# AmiExtFDD.net
KiCad netlist of a schematic drawn in EAGLE
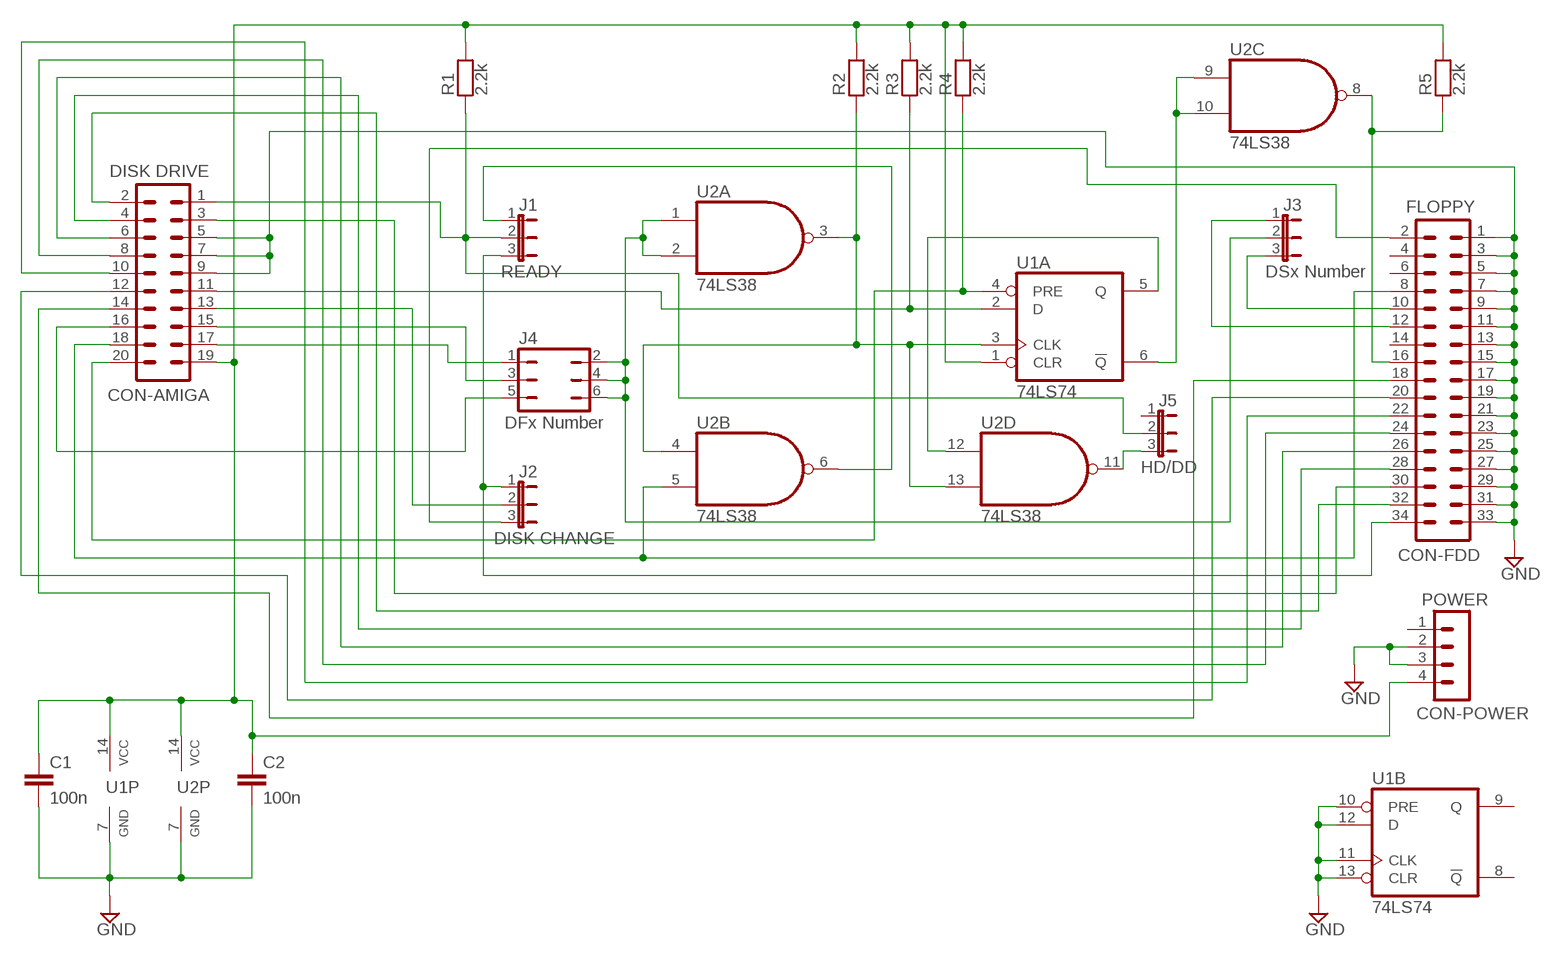
[diagram p0: schematic, sheet 1]

(export (version "E")
  (design (tool "Eeschema 10.0.6"))
  (components
    (comp (ref "C1")
      (value "100n")
      (footprint "eagle-import:SMD-UNI")
      (libsource (lib "eagle-import") (part "PAD-C5SMD"))
    )
    (comp (ref "C2")
      (value "100n")
      (footprint "eagle-import:SMD-UNI")
      (libsource (lib "eagle-import") (part "PAD-C5SMD"))
    )
    (comp (ref "CON-AMIGA")
      (value "DISK DRIVE")
      (footprint "eagle-import:IDC20")
      (libsource (lib "eagle-import") (part "IDC20"))
    )
    (comp (ref "CON-FDD")
      (value "FLOPPY")
      (footprint "eagle-import:FDD2")
      (libsource (lib "eagle-import") (part "FDD2"))
    )
    (comp (ref "CON-POWER")
      (value "POWER")
      (footprint "eagle-import:MINI-MOLEX")
      (libsource (lib "eagle-import") (part "MIN-MOLEX"))
    )
    (comp (ref "J1")
      (value "READY")
      (footprint "eagle-import:JP3X1-UNI")
      (libsource (lib "eagle-import") (part "PAD-JP3X1UNI"))
    )
    (comp (ref "J2")
      (value "DISK CHANGE")
      (footprint "eagle-import:JP3X1-UNI")
      (libsource (lib "eagle-import") (part "PAD-JP3X1UNI"))
    )
    (comp (ref "J3")
      (value "DSx Number")
      (footprint "eagle-import:JP3X1-UNI")
      (libsource (lib "eagle-import") (part "PAD-JP3X1UNI"))
    )
    (comp (ref "J4")
      (value "DFx Number")
      (footprint "eagle-import:JP3X2-UNI")
      (libsource (lib "eagle-import") (part "PAD-JP3X2UNI"))
    )
    (comp (ref "J5")
      (value "HD/DD")
      (footprint "eagle-import:JP3X1-UNI")
      (libsource (lib "eagle-import") (part "PAD-JP3X1UNI"))
    )
    (comp (ref "R1")
      (value "2.2k")
      (footprint "eagle-import:SMD-UNI")
      (libsource (lib "eagle-import") (part "PAD-R10SMD"))
    )
    (comp (ref "R2")
      (value "2.2k")
      (footprint "eagle-import:SMD-UNI")
      (libsource (lib "eagle-import") (part "PAD-R10SMD"))
    )
    (comp (ref "R3")
      (value "2.2k")
      (footprint "eagle-import:SMD-UNI")
      (libsource (lib "eagle-import") (part "PAD-R10SMD"))
    )
    (comp (ref "R4")
      (value "2.2k")
      (footprint "eagle-import:SMD-UNI")
      (libsource (lib "eagle-import") (part "PAD-R10SMD"))
    )
    (comp (ref "R5")
      (value "2.2k")
      (footprint "eagle-import:SMD-UNI")
      (libsource (lib "eagle-import") (part "PAD-R10SMD"))
    )
    (comp (ref "U1")
      (value "74LS74")
      (footprint "eagle-import:SO14")
      (libsource (lib "eagle-import") (part "PAD-7474SO14"))
    )
    (comp (ref "U2")
      (value "74LS38")
      (footprint "eagle-import:SO14")
      (libsource (lib "eagle-import") (part "PAD-7438SO14"))
    )
  )
  (nets
    (net (code "1") (name "/1") (class "Default")
      (node (ref "CON-POWER") (pin "1") (pinfunction "1_1") (pintype "power_in"))
    )
    (net (code "2") (name "GND") (class "Default")
      (node (ref "C1") (pin "2") (pinfunction "2_2") (pintype "passive"))
      (node (ref "C2") (pin "2") (pinfunction "2_2") (pintype "passive"))
      (node (ref "CON-AMIGA") (pin "5") (pinfunction "5_5") (pintype "passive"))
      (node (ref "CON-AMIGA") (pin "7") (pinfunction "7_7") (pintype "passive"))
      (node (ref "CON-AMIGA") (pin "9") (pinfunction "9_9") (pintype "power_in"))
      (node (ref "CON-FDD") (pin "1") (pinfunction "1_1") (pintype "passive"))
      (node (ref "CON-FDD") (pin "11") (pinfunction "11_11") (pintype "passive"))
      (node (ref "CON-FDD") (pin "13") (pinfunction "13_13") (pintype "passive"))
      (node (ref "CON-FDD") (pin "15") (pinfunction "15_15") (pintype "passive"))
      (node (ref "CON-FDD") (pin "17") (pinfunction "17_17") (pintype "passive"))
      (node (ref "CON-FDD") (pin "19") (pinfunction "19_19") (pintype "passive"))
      (node (ref "CON-FDD") (pin "21") (pinfunction "21_21") (pintype "passive"))
      (node (ref "CON-FDD") (pin "23") (pinfunction "23_23") (pintype "passive"))
      (node (ref "CON-FDD") (pin "25") (pinfunction "25_25") (pintype "passive"))
      (node (ref "CON-FDD") (pin "27") (pinfunction "27_27") (pintype "passive"))
      (node (ref "CON-FDD") (pin "29") (pinfunction "29_29") (pintype "passive"))
      (node (ref "CON-FDD") (pin "3") (pinfunction "3_3") (pintype "passive"))
      (node (ref "CON-FDD") (pin "31") (pinfunction "31_31") (pintype "passive"))
      (node (ref "CON-FDD") (pin "33") (pinfunction "33_33") (pintype "passive"))
      (node (ref "CON-FDD") (pin "5") (pinfunction "5_5") (pintype "passive"))
      (node (ref "CON-FDD") (pin "7") (pinfunction "7_7") (pintype "passive"))
      (node (ref "CON-FDD") (pin "9") (pinfunction "9_9") (pintype "passive"))
      (node (ref "CON-POWER") (pin "2") (pinfunction "2_2") (pintype "power_in"))
      (node (ref "CON-POWER") (pin "3") (pinfunction "3_3") (pintype "power_in"))
      (node (ref "U1") (pin "10") (pinfunction "PRE_10") (pintype "input"))
      (node (ref "U1") (pin "11") (pinfunction "CLK_11") (pintype "input"))
      (node (ref "U1") (pin "12") (pinfunction "D_12") (pintype "input"))
      (node (ref "U1") (pin "13") (pinfunction "CLR_13") (pintype "input"))
      (node (ref "U1") (pin "7") (pinfunction "GND_7") (pintype "power_in"))
      (node (ref "U2") (pin "7") (pinfunction "GND_7") (pintype "power_in"))
    )
    (net (code "3") (name "Net-(CON-AMIGA-Pad1)") (class "Default")
      (node (ref "CON-AMIGA") (pin "1") (pinfunction "1_1") (pintype "power_in"))
      (node (ref "J1") (pin "2") (pinfunction "2_2") (pintype "passive"))
      (node (ref "J5") (pin "2") (pinfunction "2_2") (pintype "passive"))
      (node (ref "R1") (pin "1") (pinfunction "1_1") (pintype "passive"))
    )
    (net (code "4") (name "Net-(CON-AMIGA-Pad2)") (class "Default")
      (node (ref "CON-AMIGA") (pin "2") (pinfunction "2_2") (pintype "passive"))
      (node (ref "CON-FDD") (pin "32") (pinfunction "32_32") (pintype "passive"))
    )
    (net (code "5") (name "Net-(CON-AMIGA-Pad3)") (class "Default")
      (node (ref "CON-AMIGA") (pin "3") (pinfunction "3_3") (pintype "passive"))
      (node (ref "CON-FDD") (pin "30") (pinfunction "30_30") (pintype "passive"))
    )
    (net (code "6") (name "Net-(CON-AMIGA-Pad4)") (class "Default")
      (node (ref "CON-AMIGA") (pin "4") (pinfunction "4_4") (pintype "passive"))
      (node (ref "CON-FDD") (pin "28") (pinfunction "28_28") (pintype "passive"))
    )
    (net (code "7") (name "Net-(CON-AMIGA-Pad6)") (class "Default")
      (node (ref "CON-AMIGA") (pin "6") (pinfunction "6_6") (pintype "passive"))
      (node (ref "CON-FDD") (pin "26") (pinfunction "26_26") (pintype "passive"))
    )
    (net (code "8") (name "Net-(CON-AMIGA-Pad8)") (class "Default")
      (node (ref "CON-AMIGA") (pin "8") (pinfunction "8_8") (pintype "passive"))
      (node (ref "CON-FDD") (pin "24") (pinfunction "24_24") (pintype "passive"))
    )
    (net (code "9") (name "Net-(CON-AMIGA-Pad10)") (class "Default")
      (node (ref "CON-AMIGA") (pin "10") (pinfunction "10_10") (pintype "passive"))
      (node (ref "CON-FDD") (pin "22") (pinfunction "22_22") (pintype "passive"))
    )
    (net (code "10") (name "Net-(CON-AMIGA-Pad12)") (class "Default")
      (node (ref "CON-AMIGA") (pin "12") (pinfunction "12_12") (pintype "passive"))
      (node (ref "CON-FDD") (pin "20") (pinfunction "20_20") (pintype "passive"))
    )
    (net (code "11") (name "Net-(CON-AMIGA-Pad13)") (class "Default")
      (node (ref "CON-AMIGA") (pin "13") (pinfunction "13_13") (pintype "passive"))
      (node (ref "J2") (pin "2") (pinfunction "2_2") (pintype "passive"))
    )
    (net (code "12") (name "Net-(CON-AMIGA-Pad14)") (class "Default")
      (node (ref "CON-AMIGA") (pin "14") (pinfunction "14_14") (pintype "passive"))
      (node (ref "CON-FDD") (pin "18") (pinfunction "18_18") (pintype "passive"))
    )
    (net (code "13") (name "Net-(CON-AMIGA-Pad15)") (class "Default")
      (node (ref "CON-AMIGA") (pin "15") (pinfunction "15_15") (pintype "passive"))
      (node (ref "J4") (pin "3") (pinfunction "3_3") (pintype "passive"))
    )
    (net (code "14") (name "Net-(CON-AMIGA-Pad16)") (class "Default")
      (node (ref "CON-AMIGA") (pin "16") (pinfunction "16_16") (pintype "passive"))
      (node (ref "J4") (pin "5") (pinfunction "5_5") (pintype "passive"))
    )
    (net (code "15") (name "Net-(CON-AMIGA-Pad17)") (class "Default")
      (node (ref "CON-AMIGA") (pin "17") (pinfunction "17_17") (pintype "passive"))
      (node (ref "J4") (pin "1") (pinfunction "1_1") (pintype "passive"))
    )
    (net (code "16") (name "Net-(CON-FDD-Pad2)") (class "Default")
      (node (ref "CON-FDD") (pin "2") (pinfunction "2_2") (pintype "passive"))
      (node (ref "J2") (pin "3") (pinfunction "3_3") (pintype "passive"))
    )
    (net (code "17") (name "Net-(CON-FDD-Pad10)") (class "Default")
      (node (ref "CON-FDD") (pin "10") (pinfunction "10_10") (pintype "passive"))
      (node (ref "J3") (pin "3") (pinfunction "3_3") (pintype "passive"))
    )
    (net (code "18") (name "Net-(CON-FDD-Pad12)") (class "Default")
      (node (ref "CON-FDD") (pin "12") (pinfunction "12_12") (pintype "passive"))
      (node (ref "J3") (pin "1") (pinfunction "1_1") (pintype "passive"))
    )
    (net (code "19") (name "Net-(CON-FDD-Pad34)") (class "Default")
      (node (ref "CON-FDD") (pin "34") (pinfunction "34_34") (pintype "passive"))
      (node (ref "J1") (pin "3") (pinfunction "3_3") (pintype "passive"))
      (node (ref "J2") (pin "1") (pinfunction "1_1") (pintype "passive"))
    )
    (net (code "20") (name "Net-(U1A-CLK)") (class "Default")
      (node (ref "R2") (pin "1") (pinfunction "1_1") (pintype "passive"))
      (node (ref "U1") (pin "3") (pinfunction "CLK_3") (pintype "input"))
      (node (ref "U2") (pin "13") (pinfunction "I1_13") (pintype "input"))
      (node (ref "U2") (pin "3") (pinfunction "O_3") (pintype "output"))
      (node (ref "U2") (pin "4") (pinfunction "I0_4") (pintype "input"))
    )
    (net (code "21") (name "Net-(U1A-CLR)") (class "Default")
      (node (ref "C1") (pin "1") (pinfunction "1_1") (pintype "passive"))
      (node (ref "C2") (pin "1") (pinfunction "1_1") (pintype "passive"))
      (node (ref "CON-AMIGA") (pin "19") (pinfunction "19_19") (pintype "passive"))
      (node (ref "CON-POWER") (pin "4") (pinfunction "4_4") (pintype "power_in"))
      (node (ref "R1") (pin "2") (pinfunction "2_2") (pintype "passive"))
      (node (ref "R2") (pin "2") (pinfunction "2_2") (pintype "passive"))
      (node (ref "R3") (pin "2") (pinfunction "2_2") (pintype "passive"))
      (node (ref "R4") (pin "2") (pinfunction "2_2") (pintype "passive"))
      (node (ref "R5") (pin "2") (pinfunction "2_2") (pintype "passive"))
      (node (ref "U1") (pin "1") (pinfunction "CLR_1") (pintype "input"))
      (node (ref "U1") (pin "14") (pinfunction "VCC_14") (pintype "power_in"))
      (node (ref "U2") (pin "14") (pinfunction "VCC_14") (pintype "power_in"))
    )
    (net (code "22") (name "Net-(U1A-D)") (class "Default")
      (node (ref "CON-AMIGA") (pin "11") (pinfunction "11_11") (pintype "passive"))
      (node (ref "R3") (pin "1") (pinfunction "1_1") (pintype "passive"))
      (node (ref "U1") (pin "2") (pinfunction "D_2") (pintype "input"))
    )
    (net (code "23") (name "Net-(U1A-PRE)") (class "Default")
      (node (ref "CON-AMIGA") (pin "20") (pinfunction "20_20") (pintype "passive"))
      (node (ref "R4") (pin "1") (pinfunction "1_1") (pintype "passive"))
      (node (ref "U1") (pin "4") (pinfunction "PRE_4") (pintype "input"))
    )
    (net (code "24") (name "Net-(U1A-Q)") (class "Default")
      (node (ref "U1") (pin "5") (pinfunction "Q_5") (pintype "output"))
      (node (ref "U2") (pin "12") (pinfunction "I0_12") (pintype "input"))
    )
    (net (code "25") (name "Net-(U1A-~{Q})") (class "Default")
      (node (ref "U1") (pin "6") (pinfunction "~{Q}_6") (pintype "output"))
      (node (ref "U2") (pin "10") (pinfunction "I1_10") (pintype "input"))
      (node (ref "U2") (pin "9") (pinfunction "I0_9") (pintype "input"))
    )
    (net (code "26") (name "Net-(U2A-I0)") (class "Default")
      (node (ref "J3") (pin "2") (pinfunction "2_2") (pintype "passive"))
      (node (ref "J4") (pin "2") (pinfunction "2_2") (pintype "passive"))
      (node (ref "J4") (pin "4") (pinfunction "4_4") (pintype "passive"))
      (node (ref "J4") (pin "6") (pinfunction "6_6") (pintype "passive"))
      (node (ref "U2") (pin "1") (pinfunction "I0_1") (pintype "input"))
      (node (ref "U2") (pin "2") (pinfunction "I1_2") (pintype "input"))
    )
    (net (code "27") (name "Net-(U2B-I1)") (class "Default")
      (node (ref "CON-AMIGA") (pin "18") (pinfunction "18_18") (pintype "passive"))
      (node (ref "CON-FDD") (pin "8") (pinfunction "8_8") (pintype "passive"))
      (node (ref "U2") (pin "5") (pinfunction "I1_5") (pintype "input"))
    )
    (net (code "28") (name "Net-(U2B-O)") (class "Default")
      (node (ref "J1") (pin "1") (pinfunction "1_1") (pintype "passive"))
      (node (ref "U2") (pin "6") (pinfunction "O_6") (pintype "output"))
    )
    (net (code "29") (name "Net-(U2C-O)") (class "Default")
      (node (ref "CON-FDD") (pin "16") (pinfunction "16_16") (pintype "passive"))
      (node (ref "R5") (pin "1") (pinfunction "1_1") (pintype "passive"))
      (node (ref "U2") (pin "8") (pinfunction "O_8") (pintype "output"))
    )
    (net (code "30") (name "Net-(U2D-O)") (class "Default")
      (node (ref "J5") (pin "3") (pinfunction "3_3") (pintype "passive"))
      (node (ref "U2") (pin "11") (pinfunction "O_11") (pintype "output"))
    )
    (net (code "31") (name "unconnected-(CON-FDD-Pad4)") (class "Default")
      (node (ref "CON-FDD") (pin "4") (pinfunction "4_4") (pintype "passive"))
    )
    (net (code "32") (name "unconnected-(CON-FDD-Pad6)") (class "Default")
      (node (ref "CON-FDD") (pin "6") (pinfunction "6_6") (pintype "passive"))
    )
    (net (code "33") (name "unconnected-(CON-FDD-Pad14)") (class "Default")
      (node (ref "CON-FDD") (pin "14") (pinfunction "14_14") (pintype "passive"))
    )
    (net (code "34") (name "unconnected-(J5-Pad1)") (class "Default")
      (node (ref "J5") (pin "1") (pinfunction "1_1") (pintype "passive"))
    )
    (net (code "35") (name "unconnected-(U1B-Q-Pad9)") (class "Default")
      (node (ref "U1") (pin "9") (pinfunction "Q_9") (pintype "output"))
    )
    (net (code "36") (name "unconnected-(U1B-~{Q}-Pad8)") (class "Default")
      (node (ref "U1") (pin "8") (pinfunction "~{Q}_8") (pintype "output"))
    )
  )
)
